# RAMA_M10-A_R1.net
KiCad netlist of a schematic drawn in EAGLE
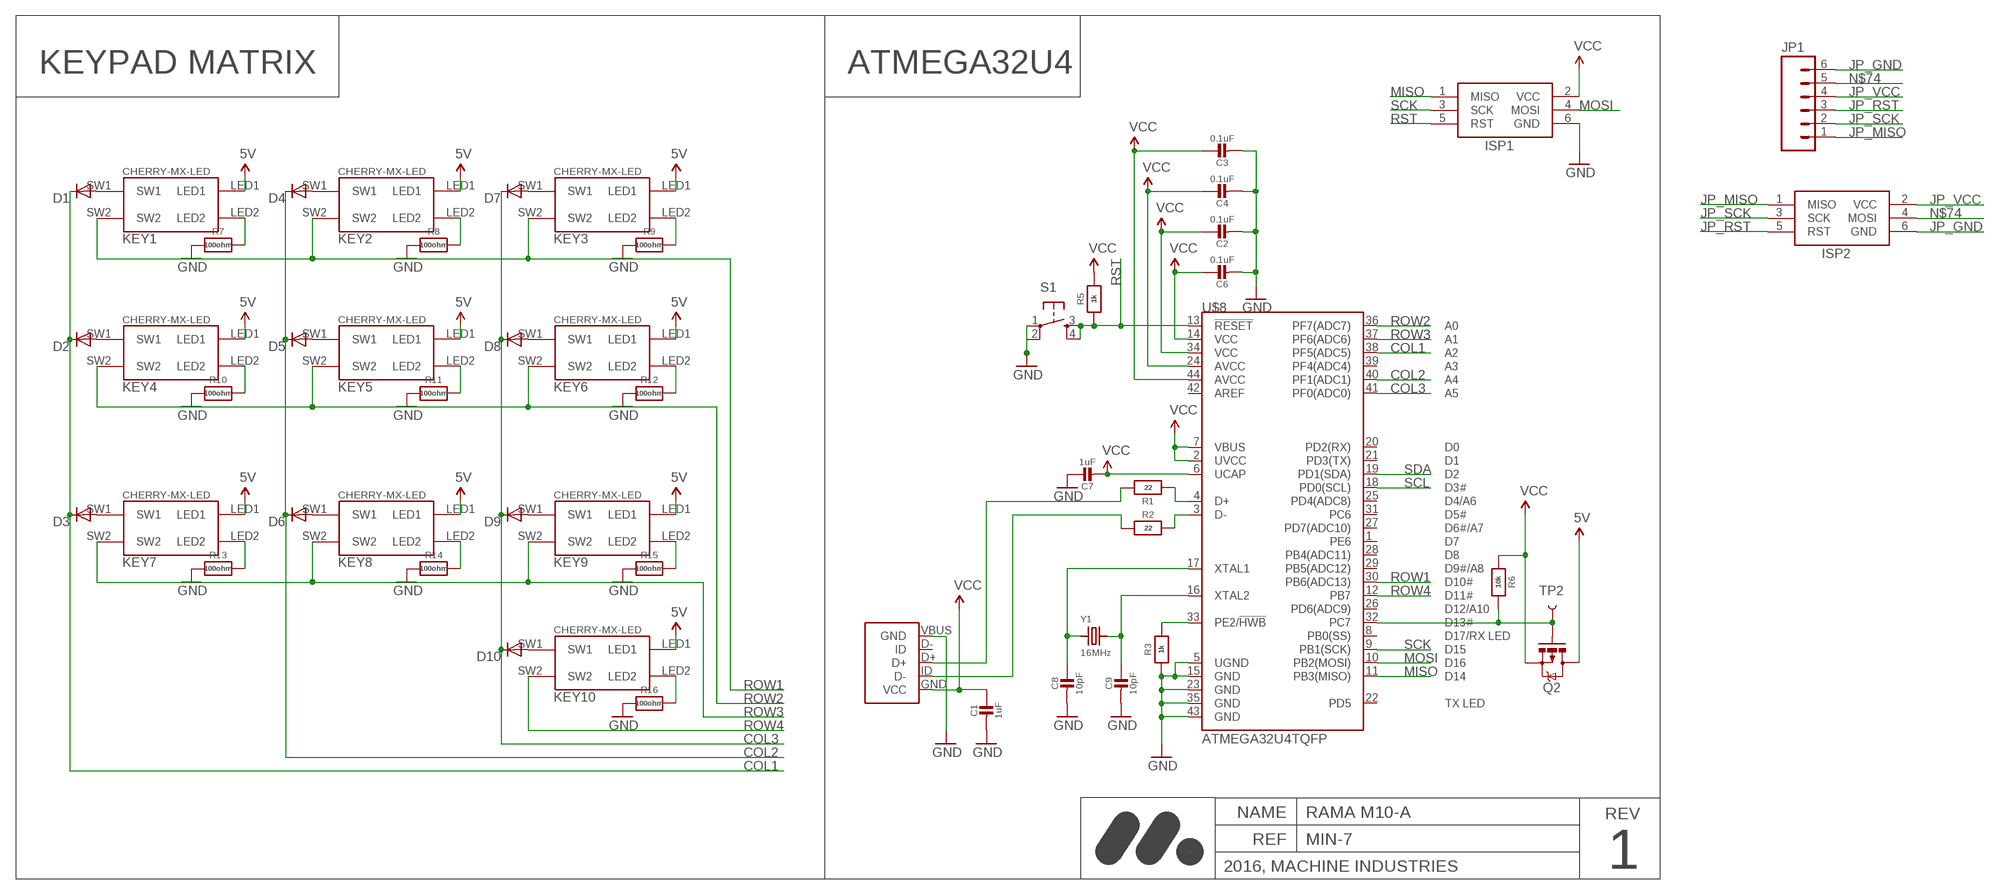
[diagram p0: schematic, sheet 1]

(export (version "E")
  (design (tool "Eeschema 10.0.6"))
  (components
    (comp (ref "C1")
      (value "1uF")
      (footprint "eagle-import:_0603MP")
      (libsource (lib "eagle-import") (part "CAP_CERAMIC_0603MP"))
    )
    (comp (ref "C2")
      (value "0.1uF")
      (footprint "eagle-import:_0603MP")
      (libsource (lib "eagle-import") (part "CAP_CERAMIC_0603MP"))
    )
    (comp (ref "C3")
      (value "0.1uF")
      (footprint "eagle-import:_0603MP")
      (libsource (lib "eagle-import") (part "CAP_CERAMIC_0603MP"))
    )
    (comp (ref "C4")
      (value "0.1uF")
      (footprint "eagle-import:_0603MP")
      (libsource (lib "eagle-import") (part "CAP_CERAMIC_0603MP"))
    )
    (comp (ref "C6")
      (value "0.1uF")
      (footprint "eagle-import:_0603MP")
      (libsource (lib "eagle-import") (part "CAP_CERAMIC_0603MP"))
    )
    (comp (ref "C7")
      (value "1uF")
      (footprint "eagle-import:_0603MP")
      (libsource (lib "eagle-import") (part "CAP_CERAMIC_0603MP"))
    )
    (comp (ref "C8")
      (value "10pF")
      (footprint "eagle-import:_0603MP")
      (libsource (lib "eagle-import") (part "CAP_CERAMIC_0603MP"))
    )
    (comp (ref "C9")
      (value "10pF")
      (footprint "eagle-import:_0603MP")
      (libsource (lib "eagle-import") (part "CAP_CERAMIC_0603MP"))
    )
    (comp (ref "D1")
      (value "DIODESOD")
      (footprint "eagle-import:SOD-323")
      (libsource (lib "eagle-import") (part "DIODESOD"))
    )
    (comp (ref "D2")
      (value "DIODESOD")
      (footprint "eagle-import:SOD-323")
      (libsource (lib "eagle-import") (part "DIODESOD"))
    )
    (comp (ref "D3")
      (value "DIODESOD")
      (footprint "eagle-import:SOD-323")
      (libsource (lib "eagle-import") (part "DIODESOD"))
    )
    (comp (ref "D4")
      (value "DIODESOD")
      (footprint "eagle-import:SOD-323")
      (libsource (lib "eagle-import") (part "DIODESOD"))
    )
    (comp (ref "D5")
      (value "DIODESOD")
      (footprint "eagle-import:SOD-323")
      (libsource (lib "eagle-import") (part "DIODESOD"))
    )
    (comp (ref "D6")
      (value "DIODESOD")
      (footprint "eagle-import:SOD-323")
      (libsource (lib "eagle-import") (part "DIODESOD"))
    )
    (comp (ref "D7")
      (value "DIODESOD")
      (footprint "eagle-import:SOD-323")
      (libsource (lib "eagle-import") (part "DIODESOD"))
    )
    (comp (ref "D8")
      (value "DIODESOD")
      (footprint "eagle-import:SOD-323")
      (libsource (lib "eagle-import") (part "DIODESOD"))
    )
    (comp (ref "D9")
      (value "DIODESOD")
      (footprint "eagle-import:SOD-323")
      (libsource (lib "eagle-import") (part "DIODESOD"))
    )
    (comp (ref "D10")
      (value "DIODESOD")
      (footprint "eagle-import:SOD-323")
      (libsource (lib "eagle-import") (part "DIODESOD"))
    )
    (comp (ref "ISP1")
      (value "AVRISP-SMT")
      (footprint "eagle-import:AVRISP-SMT")
      (libsource (lib "eagle-import") (part "AVRISP-SMT"))
    )
    (comp (ref "ISP2")
      (value "AVRISP-SMT")
      (footprint "eagle-import:AVRISP-SMT")
      (libsource (lib "eagle-import") (part "AVRISP-SMT"))
    )
    (comp (ref "JP1")
      (value "M06SIP")
      (footprint "eagle-import:1X06")
      (libsource (lib "eagle-import") (part "M06SIP"))
    )
    (comp (ref "KEY1")
      (value "CHERRY-MX-LED-18X18")
      (footprint "eagle-import:CHERRY-MX-LED-18X18")
      (libsource (lib "eagle-import") (part "CHERRY-MX-LED-18X18"))
    )
    (comp (ref "KEY2")
      (value "CHERRY-MX-LED-18X18")
      (footprint "eagle-import:CHERRY-MX-LED-18X18")
      (libsource (lib "eagle-import") (part "CHERRY-MX-LED-18X18"))
    )
    (comp (ref "KEY3")
      (value "CHERRY-MX-LED-18X18")
      (footprint "eagle-import:CHERRY-MX-LED-18X18")
      (libsource (lib "eagle-import") (part "CHERRY-MX-LED-18X18"))
    )
    (comp (ref "KEY4")
      (value "CHERRY-MX-LED-18X18")
      (footprint "eagle-import:CHERRY-MX-LED-18X18")
      (libsource (lib "eagle-import") (part "CHERRY-MX-LED-18X18"))
    )
    (comp (ref "KEY5")
      (value "CHERRY-MX-LED-18X18")
      (footprint "eagle-import:CHERRY-MX-LED-18X18")
      (libsource (lib "eagle-import") (part "CHERRY-MX-LED-18X18"))
    )
    (comp (ref "KEY6")
      (value "CHERRY-MX-LED-18X18")
      (footprint "eagle-import:CHERRY-MX-LED-18X18")
      (libsource (lib "eagle-import") (part "CHERRY-MX-LED-18X18"))
    )
    (comp (ref "KEY7")
      (value "CHERRY-MX-LED-18X18")
      (footprint "eagle-import:CHERRY-MX-LED-18X18")
      (libsource (lib "eagle-import") (part "CHERRY-MX-LED-18X18"))
    )
    (comp (ref "KEY8")
      (value "CHERRY-MX-LED-18X18")
      (footprint "eagle-import:CHERRY-MX-LED-18X18")
      (libsource (lib "eagle-import") (part "CHERRY-MX-LED-18X18"))
    )
    (comp (ref "KEY9")
      (value "CHERRY-MX-LED-18X18")
      (footprint "eagle-import:CHERRY-MX-LED-18X18")
      (libsource (lib "eagle-import") (part "CHERRY-MX-LED-18X18"))
    )
    (comp (ref "KEY10")
      (value "CHERRY-MX-LED-18X18")
      (footprint "eagle-import:CHERRY-MX-LED-18X18")
      (libsource (lib "eagle-import") (part "CHERRY-MX-LED-18X18"))
    )
    (comp (ref "Q2")
      (value "PCHANNEL-MOSFET")
      (footprint "eagle-import:SOT23-3")
      (libsource (lib "eagle-import") (part "MOSFET-PCHANNELSMD"))
    )
    (comp (ref "R1")
      (value "22")
      (footprint "eagle-import:_0603MP")
      (libsource (lib "eagle-import") (part "RESISTOR_0603MP"))
    )
    (comp (ref "R2")
      (value "22")
      (footprint "eagle-import:_0603MP")
      (libsource (lib "eagle-import") (part "RESISTOR_0603MP"))
    )
    (comp (ref "R3")
      (value "1k")
      (footprint "eagle-import:_0603MP")
      (libsource (lib "eagle-import") (part "RESISTOR_0603MP"))
    )
    (comp (ref "R5")
      (value "1k")
      (footprint "eagle-import:_0603MP")
      (libsource (lib "eagle-import") (part "RESISTOR_0603MP"))
    )
    (comp (ref "R6")
      (value "10k")
      (footprint "eagle-import:_0603MP")
      (libsource (lib "eagle-import") (part "RESISTOR_0603MP"))
    )
    (comp (ref "R7")
      (value "100ohm")
      (footprint "eagle-import:_0603MP")
      (libsource (lib "eagle-import") (part "RESISTOR_0603MP"))
    )
    (comp (ref "R8")
      (value "100ohm")
      (footprint "eagle-import:_0603MP")
      (libsource (lib "eagle-import") (part "RESISTOR_0603MP"))
    )
    (comp (ref "R9")
      (value "100ohm")
      (footprint "eagle-import:_0603MP")
      (libsource (lib "eagle-import") (part "RESISTOR_0603MP"))
    )
    (comp (ref "R10")
      (value "100ohm")
      (footprint "eagle-import:_0603MP")
      (libsource (lib "eagle-import") (part "RESISTOR_0603MP"))
    )
    (comp (ref "R11")
      (value "100ohm")
      (footprint "eagle-import:_0603MP")
      (libsource (lib "eagle-import") (part "RESISTOR_0603MP"))
    )
    (comp (ref "R12")
      (value "100ohm")
      (footprint "eagle-import:_0603MP")
      (libsource (lib "eagle-import") (part "RESISTOR_0603MP"))
    )
    (comp (ref "R13")
      (value "100ohm")
      (footprint "eagle-import:_0603MP")
      (libsource (lib "eagle-import") (part "RESISTOR_0603MP"))
    )
    (comp (ref "R14")
      (value "100ohm")
      (footprint "eagle-import:_0603MP")
      (libsource (lib "eagle-import") (part "RESISTOR_0603MP"))
    )
    (comp (ref "R15")
      (value "100ohm")
      (footprint "eagle-import:_0603MP")
      (libsource (lib "eagle-import") (part "RESISTOR_0603MP"))
    )
    (comp (ref "R16")
      (value "100ohm")
      (footprint "eagle-import:_0603MP")
      (libsource (lib "eagle-import") (part "RESISTOR_0603MP"))
    )
    (comp (ref "S1")
      (value "TAC_SWITCHSMD")
      (footprint "eagle-import:TACTILE_SWITCH_SMD")
      (libsource (lib "eagle-import") (part "TAC_SWITCHSMD"))
    )
    (comp (ref "TP2")
      (value "TEST-POINT3")
      (footprint "eagle-import:PAD.03X.03")
      (libsource (lib "eagle-import") (part "TEST-POINT3"))
    )
    (comp (ref "U$8")
      (value "ATMEGA32U4TQFP")
      (footprint "eagle-import:SPARKFUN-DIGITALIC_TQFP44")
      (libsource (lib "eagle-import") (part "ATMEGA32U4TQFP"))
    )
    (comp (ref "U$9")
      (value "MICRO-USB-B-FEMALE")
      (footprint "eagle-import:10118192-0001LF")
      (libsource (lib "eagle-import") (part "MICRO-USB-B-FEMALE"))
    )
    (comp (ref "Y1")
      (value "16MHz")
      (footprint "eagle-import:CRYSTAL_3.2X2.5")
      (libsource (lib "eagle-import") (part "CRYSTAL3.2X2.5"))
    )
  )
  (nets
    (net (code "1") (name "/COL1") (class "Default")
      (node (ref "D1") (pin "1") (pinfunction "C_1") (pintype "passive"))
      (node (ref "D2") (pin "1") (pinfunction "C_1") (pintype "passive"))
      (node (ref "D3") (pin "1") (pinfunction "C_1") (pintype "passive"))
      (node (ref "U$8") (pin "38") (pinfunction "PF5(ADC5)_38") (pintype "bidirectional"))
    )
    (net (code "2") (name "/COL2") (class "Default")
      (node (ref "D4") (pin "1") (pinfunction "C_1") (pintype "passive"))
      (node (ref "D5") (pin "1") (pinfunction "C_1") (pintype "passive"))
      (node (ref "D6") (pin "1") (pinfunction "C_1") (pintype "passive"))
      (node (ref "U$8") (pin "40") (pinfunction "PF1(ADC1)_40") (pintype "bidirectional"))
    )
    (net (code "3") (name "/COL3") (class "Default")
      (node (ref "D10") (pin "1") (pinfunction "C_1") (pintype "passive"))
      (node (ref "D7") (pin "1") (pinfunction "C_1") (pintype "passive"))
      (node (ref "D8") (pin "1") (pinfunction "C_1") (pintype "passive"))
      (node (ref "D9") (pin "1") (pinfunction "C_1") (pintype "passive"))
      (node (ref "U$8") (pin "41") (pinfunction "PF0(ADC0)_41") (pintype "bidirectional"))
    )
    (net (code "4") (name "/JP_GND") (class "Default")
      (node (ref "ISP2") (pin "6") (pinfunction "GND_6") (pintype "power_in"))
      (node (ref "JP1") (pin "6") (pinfunction "6_6") (pintype "passive"))
    )
    (net (code "5") (name "/JP_MISO") (class "Default")
      (node (ref "ISP2") (pin "1") (pinfunction "MISO_1") (pintype "input"))
      (node (ref "JP1") (pin "1") (pinfunction "1_1") (pintype "passive"))
    )
    (net (code "6") (name "/JP_RST") (class "Default")
      (node (ref "ISP2") (pin "5") (pinfunction "RST_5") (pintype "output"))
      (node (ref "JP1") (pin "3") (pinfunction "3_3") (pintype "passive"))
    )
    (net (code "7") (name "/JP_SCK") (class "Default")
      (node (ref "ISP2") (pin "3") (pinfunction "SCK_3") (pintype "output"))
      (node (ref "JP1") (pin "2") (pinfunction "2_2") (pintype "passive"))
    )
    (net (code "8") (name "/JP_VCC") (class "Default")
      (node (ref "ISP2") (pin "2") (pinfunction "VCC_2") (pintype "power_in"))
      (node (ref "JP1") (pin "4") (pinfunction "4_4") (pintype "passive"))
    )
    (net (code "9") (name "/MISO") (class "Default")
      (node (ref "ISP1") (pin "1") (pinfunction "MISO_1") (pintype "input"))
      (node (ref "U$8") (pin "11") (pinfunction "PB3(MISO)_11") (pintype "bidirectional"))
    )
    (net (code "10") (name "/MOSI") (class "Default")
      (node (ref "ISP1") (pin "4") (pinfunction "MOSI_4") (pintype "output"))
      (node (ref "U$8") (pin "10") (pinfunction "PB2(MOSI)_10") (pintype "bidirectional"))
    )
    (net (code "11") (name "/N$74") (class "Default")
      (node (ref "ISP2") (pin "4") (pinfunction "MOSI_4") (pintype "output"))
      (node (ref "JP1") (pin "5") (pinfunction "5_5") (pintype "passive"))
    )
    (net (code "12") (name "/ROW1") (class "Default")
      (node (ref "KEY1") (pin "SW2") (pinfunction "SW2_SW2") (pintype "bidirectional"))
      (node (ref "KEY2") (pin "SW2") (pinfunction "SW2_SW2") (pintype "bidirectional"))
      (node (ref "KEY3") (pin "SW2") (pinfunction "SW2_SW2") (pintype "bidirectional"))
      (node (ref "U$8") (pin "30") (pinfunction "PB6(ADC13)_30") (pintype "bidirectional"))
    )
    (net (code "13") (name "/ROW2") (class "Default")
      (node (ref "KEY4") (pin "SW2") (pinfunction "SW2_SW2") (pintype "bidirectional"))
      (node (ref "KEY5") (pin "SW2") (pinfunction "SW2_SW2") (pintype "bidirectional"))
      (node (ref "KEY6") (pin "SW2") (pinfunction "SW2_SW2") (pintype "bidirectional"))
      (node (ref "U$8") (pin "36") (pinfunction "PF7(ADC7)_36") (pintype "bidirectional"))
    )
    (net (code "14") (name "/ROW3") (class "Default")
      (node (ref "KEY7") (pin "SW2") (pinfunction "SW2_SW2") (pintype "bidirectional"))
      (node (ref "KEY8") (pin "SW2") (pinfunction "SW2_SW2") (pintype "bidirectional"))
      (node (ref "KEY9") (pin "SW2") (pinfunction "SW2_SW2") (pintype "bidirectional"))
      (node (ref "U$8") (pin "37") (pinfunction "PF6(ADC6)_37") (pintype "bidirectional"))
    )
    (net (code "15") (name "/ROW4") (class "Default")
      (node (ref "KEY10") (pin "SW2") (pinfunction "SW2_SW2") (pintype "bidirectional"))
      (node (ref "U$8") (pin "12") (pinfunction "PB7_12") (pintype "bidirectional"))
    )
    (net (code "16") (name "/RST") (class "Default")
      (node (ref "ISP1") (pin "5") (pinfunction "RST_5") (pintype "output"))
      (node (ref "R5") (pin "1") (pinfunction "1_1") (pintype "passive"))
      (node (ref "S1") (pin "3") (pinfunction "3_3") (pintype "passive"))
      (node (ref "S1") (pin "4") (pinfunction "4_4") (pintype "passive"))
      (node (ref "U$8") (pin "13") (pinfunction "~{RESET}_13") (pintype "bidirectional"))
    )
    (net (code "17") (name "/SCK") (class "Default")
      (node (ref "ISP1") (pin "3") (pinfunction "SCK_3") (pintype "output"))
      (node (ref "U$8") (pin "9") (pinfunction "PB1(SCK)_9") (pintype "bidirectional"))
    )
    (net (code "18") (name "/SCL") (class "Default")
      (node (ref "U$8") (pin "18") (pinfunction "PD0(SCL)_18") (pintype "bidirectional"))
    )
    (net (code "19") (name "/SDA") (class "Default")
      (node (ref "U$8") (pin "19") (pinfunction "PD1(SDA)_19") (pintype "bidirectional"))
    )
    (net (code "20") (name "5V") (class "Default")
      (node (ref "KEY1") (pin "LED1") (pinfunction "LED1_LED1") (pintype "bidirectional"))
      (node (ref "KEY10") (pin "LED1") (pinfunction "LED1_LED1") (pintype "bidirectional"))
      (node (ref "KEY2") (pin "LED1") (pinfunction "LED1_LED1") (pintype "bidirectional"))
      (node (ref "KEY3") (pin "LED1") (pinfunction "LED1_LED1") (pintype "bidirectional"))
      (node (ref "KEY4") (pin "LED1") (pinfunction "LED1_LED1") (pintype "bidirectional"))
      (node (ref "KEY5") (pin "LED1") (pinfunction "LED1_LED1") (pintype "bidirectional"))
      (node (ref "KEY6") (pin "LED1") (pinfunction "LED1_LED1") (pintype "bidirectional"))
      (node (ref "KEY7") (pin "LED1") (pinfunction "LED1_LED1") (pintype "bidirectional"))
      (node (ref "KEY8") (pin "LED1") (pinfunction "LED1_LED1") (pintype "bidirectional"))
      (node (ref "KEY9") (pin "LED1") (pinfunction "LED1_LED1") (pintype "bidirectional"))
      (node (ref "Q2") (pin "3") (pinfunction "D_3") (pintype "passive"))
    )
    (net (code "21") (name "GND") (class "Default")
      (node (ref "C1") (pin "2") (pinfunction "2_2") (pintype "passive"))
      (node (ref "C2") (pin "2") (pinfunction "2_2") (pintype "passive"))
      (node (ref "C3") (pin "2") (pinfunction "2_2") (pintype "passive"))
      (node (ref "C4") (pin "2") (pinfunction "2_2") (pintype "passive"))
      (node (ref "C6") (pin "2") (pinfunction "2_2") (pintype "passive"))
      (node (ref "C7") (pin "1") (pinfunction "1_1") (pintype "passive"))
      (node (ref "C8") (pin "2") (pinfunction "2_2") (pintype "passive"))
      (node (ref "C9") (pin "2") (pinfunction "2_2") (pintype "passive"))
      (node (ref "ISP1") (pin "6") (pinfunction "GND_6") (pintype "power_in"))
      (node (ref "R10") (pin "1") (pinfunction "1_1") (pintype "passive"))
      (node (ref "R11") (pin "1") (pinfunction "1_1") (pintype "passive"))
      (node (ref "R12") (pin "1") (pinfunction "1_1") (pintype "passive"))
      (node (ref "R13") (pin "1") (pinfunction "1_1") (pintype "passive"))
      (node (ref "R14") (pin "1") (pinfunction "1_1") (pintype "passive"))
      (node (ref "R15") (pin "1") (pinfunction "1_1") (pintype "passive"))
      (node (ref "R16") (pin "1") (pinfunction "1_1") (pintype "passive"))
      (node (ref "R3") (pin "1") (pinfunction "1_1") (pintype "passive"))
      (node (ref "R7") (pin "1") (pinfunction "1_1") (pintype "passive"))
      (node (ref "R8") (pin "1") (pinfunction "1_1") (pintype "passive"))
      (node (ref "R9") (pin "1") (pinfunction "1_1") (pintype "passive"))
      (node (ref "S1") (pin "1") (pinfunction "1_1") (pintype "passive"))
      (node (ref "S1") (pin "2") (pinfunction "2_2") (pintype "passive"))
      (node (ref "U$8") (pin "15") (pinfunction "GND_15") (pintype "bidirectional"))
      (node (ref "U$8") (pin "23") (pinfunction "GND_23") (pintype "bidirectional"))
      (node (ref "U$8") (pin "35") (pinfunction "GND_35") (pintype "bidirectional"))
      (node (ref "U$8") (pin "43") (pinfunction "GND_43") (pintype "bidirectional"))
      (node (ref "U$8") (pin "5") (pinfunction "UGND_5") (pintype "bidirectional"))
      (node (ref "U$9") (pin "VBUS") (pinfunction "GND_VBUS") (pintype "bidirectional"))
    )
    (net (code "22") (name "Net-(D1-A)") (class "Default")
      (node (ref "D1") (pin "2") (pinfunction "A_2") (pintype "passive"))
      (node (ref "KEY1") (pin "SW1") (pinfunction "SW1_SW1") (pintype "bidirectional"))
    )
    (net (code "23") (name "Net-(D2-A)") (class "Default")
      (node (ref "D2") (pin "2") (pinfunction "A_2") (pintype "passive"))
      (node (ref "KEY4") (pin "SW1") (pinfunction "SW1_SW1") (pintype "bidirectional"))
    )
    (net (code "24") (name "Net-(D3-A)") (class "Default")
      (node (ref "D3") (pin "2") (pinfunction "A_2") (pintype "passive"))
      (node (ref "KEY7") (pin "SW1") (pinfunction "SW1_SW1") (pintype "bidirectional"))
    )
    (net (code "25") (name "Net-(D4-A)") (class "Default")
      (node (ref "D4") (pin "2") (pinfunction "A_2") (pintype "passive"))
      (node (ref "KEY2") (pin "SW1") (pinfunction "SW1_SW1") (pintype "bidirectional"))
    )
    (net (code "26") (name "Net-(D5-A)") (class "Default")
      (node (ref "D5") (pin "2") (pinfunction "A_2") (pintype "passive"))
      (node (ref "KEY5") (pin "SW1") (pinfunction "SW1_SW1") (pintype "bidirectional"))
    )
    (net (code "27") (name "Net-(D6-A)") (class "Default")
      (node (ref "D6") (pin "2") (pinfunction "A_2") (pintype "passive"))
      (node (ref "KEY8") (pin "SW1") (pinfunction "SW1_SW1") (pintype "bidirectional"))
    )
    (net (code "28") (name "Net-(D7-A)") (class "Default")
      (node (ref "D7") (pin "2") (pinfunction "A_2") (pintype "passive"))
      (node (ref "KEY3") (pin "SW1") (pinfunction "SW1_SW1") (pintype "bidirectional"))
    )
    (net (code "29") (name "Net-(D8-A)") (class "Default")
      (node (ref "D8") (pin "2") (pinfunction "A_2") (pintype "passive"))
      (node (ref "KEY6") (pin "SW1") (pinfunction "SW1_SW1") (pintype "bidirectional"))
    )
    (net (code "30") (name "Net-(D9-A)") (class "Default")
      (node (ref "D9") (pin "2") (pinfunction "A_2") (pintype "passive"))
      (node (ref "KEY9") (pin "SW1") (pinfunction "SW1_SW1") (pintype "bidirectional"))
    )
    (net (code "31") (name "Net-(D10-A)") (class "Default")
      (node (ref "D10") (pin "2") (pinfunction "A_2") (pintype "passive"))
      (node (ref "KEY10") (pin "SW1") (pinfunction "SW1_SW1") (pintype "bidirectional"))
    )
    (net (code "32") (name "Net-(KEY1-PadLED2)") (class "Default")
      (node (ref "KEY1") (pin "LED2") (pinfunction "LED2_LED2") (pintype "bidirectional"))
      (node (ref "R7") (pin "2") (pinfunction "2_2") (pintype "passive"))
    )
    (net (code "33") (name "Net-(KEY2-PadLED2)") (class "Default")
      (node (ref "KEY2") (pin "LED2") (pinfunction "LED2_LED2") (pintype "bidirectional"))
      (node (ref "R8") (pin "2") (pinfunction "2_2") (pintype "passive"))
    )
    (net (code "34") (name "Net-(KEY3-PadLED2)") (class "Default")
      (node (ref "KEY3") (pin "LED2") (pinfunction "LED2_LED2") (pintype "bidirectional"))
      (node (ref "R9") (pin "2") (pinfunction "2_2") (pintype "passive"))
    )
    (net (code "35") (name "Net-(KEY4-PadLED2)") (class "Default")
      (node (ref "KEY4") (pin "LED2") (pinfunction "LED2_LED2") (pintype "bidirectional"))
      (node (ref "R10") (pin "2") (pinfunction "2_2") (pintype "passive"))
    )
    (net (code "36") (name "Net-(KEY5-PadLED2)") (class "Default")
      (node (ref "KEY5") (pin "LED2") (pinfunction "LED2_LED2") (pintype "bidirectional"))
      (node (ref "R11") (pin "2") (pinfunction "2_2") (pintype "passive"))
    )
    (net (code "37") (name "Net-(KEY6-PadLED2)") (class "Default")
      (node (ref "KEY6") (pin "LED2") (pinfunction "LED2_LED2") (pintype "bidirectional"))
      (node (ref "R12") (pin "2") (pinfunction "2_2") (pintype "passive"))
    )
    (net (code "38") (name "Net-(KEY7-PadLED2)") (class "Default")
      (node (ref "KEY7") (pin "LED2") (pinfunction "LED2_LED2") (pintype "bidirectional"))
      (node (ref "R13") (pin "2") (pinfunction "2_2") (pintype "passive"))
    )
    (net (code "39") (name "Net-(KEY8-PadLED2)") (class "Default")
      (node (ref "KEY8") (pin "LED2") (pinfunction "LED2_LED2") (pintype "bidirectional"))
      (node (ref "R14") (pin "2") (pinfunction "2_2") (pintype "passive"))
    )
    (net (code "40") (name "Net-(KEY9-PadLED2)") (class "Default")
      (node (ref "KEY9") (pin "LED2") (pinfunction "LED2_LED2") (pintype "bidirectional"))
      (node (ref "R15") (pin "2") (pinfunction "2_2") (pintype "passive"))
    )
    (net (code "41") (name "Net-(KEY10-PadLED2)") (class "Default")
      (node (ref "KEY10") (pin "LED2") (pinfunction "LED2_LED2") (pintype "bidirectional"))
      (node (ref "R16") (pin "2") (pinfunction "2_2") (pintype "passive"))
    )
    (net (code "42") (name "Net-(Q2-G)") (class "Default")
      (node (ref "Q2") (pin "1") (pinfunction "G_1") (pintype "passive"))
      (node (ref "R6") (pin "2") (pinfunction "2_2") (pintype "passive"))
      (node (ref "TP2") (pin "P$1") (pinfunction "1_P$1") (pintype "bidirectional"))
      (node (ref "U$8") (pin "32") (pinfunction "PC7_32") (pintype "bidirectional"))
    )
    (net (code "43") (name "Net-(R1-Pad1)") (class "Default")
      (node (ref "R1") (pin "1") (pinfunction "1_1") (pintype "passive"))
      (node (ref "U$9") (pin "D+") (pinfunction "D+_D+") (pintype "bidirectional"))
    )
    (net (code "44") (name "Net-(U$8-D+)") (class "Default")
      (node (ref "R1") (pin "2") (pinfunction "2_2") (pintype "passive"))
      (node (ref "U$8") (pin "4") (pinfunction "D+_4") (pintype "bidirectional"))
    )
    (net (code "45") (name "Net-(U$8-D-)") (class "Default")
      (node (ref "R2") (pin "2") (pinfunction "2_2") (pintype "passive"))
      (node (ref "U$8") (pin "3") (pinfunction "D-_3") (pintype "bidirectional"))
    )
    (net (code "46") (name "Net-(U$8-PE2{slash}~{HWB})") (class "Default")
      (node (ref "R3") (pin "2") (pinfunction "2_2") (pintype "passive"))
      (node (ref "U$8") (pin "33") (pinfunction "PE2/~{HWB}_33") (pintype "bidirectional"))
    )
    (net (code "47") (name "Net-(U$8-XTAL1)") (class "Default")
      (node (ref "C8") (pin "1") (pinfunction "1_1") (pintype "passive"))
      (node (ref "U$8") (pin "17") (pinfunction "XTAL1_17") (pintype "bidirectional"))
      (node (ref "Y1") (pin "1") (pinfunction "1_1") (pintype "passive"))
    )
    (net (code "48") (name "Net-(U$8-XTAL2)") (class "Default")
      (node (ref "C9") (pin "1") (pinfunction "1_1") (pintype "passive"))
      (node (ref "U$8") (pin "16") (pinfunction "XTAL2_16") (pintype "bidirectional"))
      (node (ref "Y1") (pin "2") (pinfunction "2_2") (pintype "passive"))
    )
    (net (code "49") (name "Net-(U$9-D-)") (class "Default")
      (node (ref "R2") (pin "1") (pinfunction "1_1") (pintype "passive"))
      (node (ref "U$9") (pin "ID") (pinfunction "D-_ID") (pintype "bidirectional"))
    )
    (net (code "50") (name "VCC") (class "Default")
      (node (ref "C1") (pin "1") (pinfunction "1_1") (pintype "passive"))
      (node (ref "C2") (pin "1") (pinfunction "1_1") (pintype "passive"))
      (node (ref "C3") (pin "1") (pinfunction "1_1") (pintype "passive"))
      (node (ref "C4") (pin "1") (pinfunction "1_1") (pintype "passive"))
      (node (ref "C6") (pin "1") (pinfunction "1_1") (pintype "passive"))
      (node (ref "C7") (pin "2") (pinfunction "2_2") (pintype "passive"))
      (node (ref "ISP1") (pin "2") (pinfunction "VCC_2") (pintype "power_in"))
      (node (ref "Q2") (pin "2") (pinfunction "S_2") (pintype "passive"))
      (node (ref "R5") (pin "2") (pinfunction "2_2") (pintype "passive"))
      (node (ref "R6") (pin "1") (pinfunction "1_1") (pintype "passive"))
      (node (ref "U$8") (pin "14") (pinfunction "VCC_14") (pintype "bidirectional"))
      (node (ref "U$8") (pin "2") (pinfunction "UVCC_2") (pintype "bidirectional"))
      (node (ref "U$8") (pin "24") (pinfunction "AVCC_24") (pintype "bidirectional"))
      (node (ref "U$8") (pin "34") (pinfunction "VCC_34") (pintype "bidirectional"))
      (node (ref "U$8") (pin "44") (pinfunction "AVCC_44") (pintype "bidirectional"))
      (node (ref "U$8") (pin "6") (pinfunction "UCAP_6") (pintype "bidirectional"))
      (node (ref "U$8") (pin "7") (pinfunction "VBUS_7") (pintype "bidirectional"))
      (node (ref "U$9") (pin "GND") (pinfunction "VCC_GND") (pintype "bidirectional"))
    )
    (net (code "51") (name "unconnected-(U$8-AREF-Pad42)") (class "Default")
      (node (ref "U$8") (pin "42") (pinfunction "AREF_42") (pintype "bidirectional"))
    )
    (net (code "52") (name "unconnected-(U$8-PB0(SS)-Pad8)") (class "Default")
      (node (ref "U$8") (pin "8") (pinfunction "PB0(SS)_8") (pintype "bidirectional"))
    )
    (net (code "53") (name "unconnected-(U$8-PB4(ADC11)-Pad28)") (class "Default")
      (node (ref "U$8") (pin "28") (pinfunction "PB4(ADC11)_28") (pintype "bidirectional"))
    )
    (net (code "54") (name "unconnected-(U$8-PB5(ADC12)-Pad29)") (class "Default")
      (node (ref "U$8") (pin "29") (pinfunction "PB5(ADC12)_29") (pintype "bidirectional"))
    )
    (net (code "55") (name "unconnected-(U$8-PC6-Pad31)") (class "Default")
      (node (ref "U$8") (pin "31") (pinfunction "PC6_31") (pintype "bidirectional"))
    )
    (net (code "56") (name "unconnected-(U$8-PD2(RX)-Pad20)") (class "Default")
      (node (ref "U$8") (pin "20") (pinfunction "PD2(RX)_20") (pintype "bidirectional"))
    )
    (net (code "57") (name "unconnected-(U$8-PD3(TX)-Pad21)") (class "Default")
      (node (ref "U$8") (pin "21") (pinfunction "PD3(TX)_21") (pintype "bidirectional"))
    )
    (net (code "58") (name "unconnected-(U$8-PD4(ADC8)-Pad25)") (class "Default")
      (node (ref "U$8") (pin "25") (pinfunction "PD4(ADC8)_25") (pintype "bidirectional"))
    )
    (net (code "59") (name "unconnected-(U$8-PD5-Pad22)") (class "Default")
      (node (ref "U$8") (pin "22") (pinfunction "PD5_22") (pintype "bidirectional"))
    )
    (net (code "60") (name "unconnected-(U$8-PD6(ADC9)-Pad26)") (class "Default")
      (node (ref "U$8") (pin "26") (pinfunction "PD6(ADC9)_26") (pintype "bidirectional"))
    )
    (net (code "61") (name "unconnected-(U$8-PD7(ADC10)-Pad27)") (class "Default")
      (node (ref "U$8") (pin "27") (pinfunction "PD7(ADC10)_27") (pintype "bidirectional"))
    )
    (net (code "62") (name "unconnected-(U$8-PE6-Pad1)") (class "Default")
      (node (ref "U$8") (pin "1") (pinfunction "PE6_1") (pintype "bidirectional"))
    )
    (net (code "63") (name "unconnected-(U$8-PF4(ADC4)-Pad39)") (class "Default")
      (node (ref "U$8") (pin "39") (pinfunction "PF4(ADC4)_39") (pintype "bidirectional"))
    )
    (net (code "64") (name "unconnected-(U$9-ID-PadD-)") (class "Default")
      (node (ref "U$9") (pin "D-") (pinfunction "ID_D-") (pintype "bidirectional"))
    )
  )
)
